# Expansor_conn.net
KiCad netlist of a schematic drawn in Altium Designer
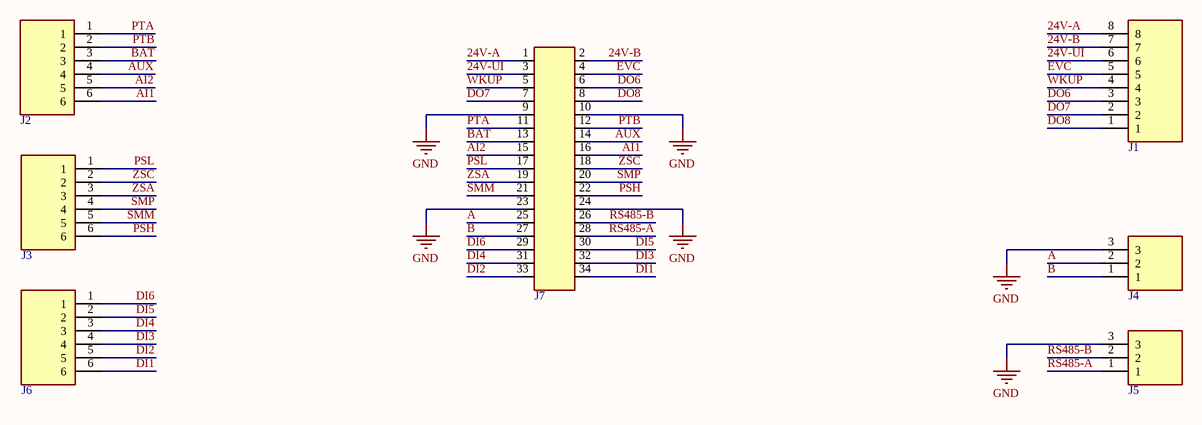
[diagram p0: Expansor_conn.SchDoc]

(export (version "E")
  (design (tool "Eeschema 10.0.6"))
  (components
    (comp (ref "J1")
      (value "HDRF8")
      (footprint "HDR_F_1X8")
      (description "CONN, HEADER, Female, pitch: 2.54mm, 8POS")
      (libsource (lib "Headers") (part "Header Female 1x8 THT"))
    )
    (comp (ref "J2")
      (value "HDRF6")
      (footprint "HDR_F_1X6")
      (description "CONN, HEADER, Female, pitch: 2.54mm, 6POS")
      (libsource (lib "Headers") (part "Header Female 1x6 THT"))
    )
    (comp (ref "J3")
      (value "HDRF6")
      (footprint "HDR_F_1X6")
      (description "CONN, HEADER, Female, pitch: 2.54mm, 6POS")
      (libsource (lib "Headers") (part "Header Female 1x6 THT"))
    )
    (comp (ref "J4")
      (value "HDRF3")
      (footprint "HDR_F_1X3")
      (description "CONN, HEADER, Female, pitch: 2.54mm, 3POS")
      (libsource (lib "Headers") (part "Header Female 1x3 THT"))
    )
    (comp (ref "J5")
      (value "HDRF3")
      (footprint "HDR_F_1X3")
      (description "CONN, HEADER, Female, pitch: 2.54mm, 3POS")
      (libsource (lib "Headers") (part "Header Female 1x3 THT"))
    )
    (comp (ref "J6")
      (value "HDRF6")
      (footprint "HDR_F_1X6")
      (description "CONN, HEADER, Female, pitch: 2.54mm, 6POS")
      (libsource (lib "Headers") (part "Header Female 1x6 THT"))
    )
    (comp (ref "J7")
      (value "6120XX21621_61203421621")
      (footprint "61203421621")
      (description "34 pins, straight, gold plating")
      (fields (field (name "MF") "Wurth Electronics") (field (name "MP") "61203421621"))
      (libsource (lib "Base_borne_MEP_1") (part "6120XX21621_61203421621"))
    )
  )
  (nets
    (net (code "1") (name "/24V-A") (class "Default")
      (node (ref "J1") (pin "8") (pinfunction "8_8") (pintype "passive"))
      (node (ref "J7") (pin "1") (pinfunction "1_1") (pintype "passive"))
    )
    (net (code "2") (name "/24V-B") (class "Default")
      (node (ref "J1") (pin "7") (pinfunction "7_7") (pintype "passive"))
      (node (ref "J7") (pin "2") (pinfunction "2_2") (pintype "passive"))
    )
    (net (code "3") (name "/24V-UI") (class "Default")
      (node (ref "J1") (pin "6") (pinfunction "6_6") (pintype "passive"))
      (node (ref "J7") (pin "3") (pinfunction "3_3") (pintype "passive"))
    )
    (net (code "4") (name "/A") (class "Default")
      (node (ref "J4") (pin "2") (pinfunction "2_2") (pintype "passive"))
      (node (ref "J7") (pin "25") (pinfunction "25_25") (pintype "passive"))
    )
    (net (code "5") (name "/AI1") (class "Default")
      (node (ref "J2") (pin "6") (pinfunction "6_6") (pintype "passive"))
      (node (ref "J7") (pin "16") (pinfunction "16_16") (pintype "passive"))
    )
    (net (code "6") (name "/AI2") (class "Default")
      (node (ref "J2") (pin "5") (pinfunction "5_5") (pintype "passive"))
      (node (ref "J7") (pin "15") (pinfunction "15_15") (pintype "passive"))
    )
    (net (code "7") (name "/AUX") (class "Default")
      (node (ref "J2") (pin "4") (pinfunction "4_4") (pintype "passive"))
      (node (ref "J7") (pin "14") (pinfunction "14_14") (pintype "passive"))
    )
    (net (code "8") (name "/B") (class "Default")
      (node (ref "J4") (pin "1") (pinfunction "1_1") (pintype "passive"))
      (node (ref "J7") (pin "27") (pinfunction "27_27") (pintype "passive"))
    )
    (net (code "9") (name "/BAT") (class "Default")
      (node (ref "J2") (pin "3") (pinfunction "3_3") (pintype "passive"))
      (node (ref "J7") (pin "13") (pinfunction "13_13") (pintype "passive"))
    )
    (net (code "10") (name "/DI1") (class "Default")
      (node (ref "J6") (pin "6") (pinfunction "6_6") (pintype "passive"))
      (node (ref "J7") (pin "34") (pinfunction "34_34") (pintype "passive"))
    )
    (net (code "11") (name "/DI2") (class "Default")
      (node (ref "J6") (pin "5") (pinfunction "5_5") (pintype "passive"))
      (node (ref "J7") (pin "33") (pinfunction "33_33") (pintype "passive"))
    )
    (net (code "12") (name "/DI3") (class "Default")
      (node (ref "J6") (pin "4") (pinfunction "4_4") (pintype "passive"))
      (node (ref "J7") (pin "32") (pinfunction "32_32") (pintype "passive"))
    )
    (net (code "13") (name "/DI4") (class "Default")
      (node (ref "J6") (pin "3") (pinfunction "3_3") (pintype "passive"))
      (node (ref "J7") (pin "31") (pinfunction "31_31") (pintype "passive"))
    )
    (net (code "14") (name "/DI5") (class "Default")
      (node (ref "J6") (pin "2") (pinfunction "2_2") (pintype "passive"))
      (node (ref "J7") (pin "30") (pinfunction "30_30") (pintype "passive"))
    )
    (net (code "15") (name "/DI6") (class "Default")
      (node (ref "J6") (pin "1") (pinfunction "1_1") (pintype "passive"))
      (node (ref "J7") (pin "29") (pinfunction "29_29") (pintype "passive"))
    )
    (net (code "16") (name "/DO6") (class "Default")
      (node (ref "J1") (pin "3") (pinfunction "3_3") (pintype "passive"))
      (node (ref "J7") (pin "6") (pinfunction "6_6") (pintype "passive"))
    )
    (net (code "17") (name "/DO7") (class "Default")
      (node (ref "J1") (pin "2") (pinfunction "2_2") (pintype "passive"))
      (node (ref "J7") (pin "7") (pinfunction "7_7") (pintype "passive"))
    )
    (net (code "18") (name "/DO8") (class "Default")
      (node (ref "J1") (pin "1") (pinfunction "1_1") (pintype "passive"))
      (node (ref "J7") (pin "8") (pinfunction "8_8") (pintype "passive"))
    )
    (net (code "19") (name "/EVC") (class "Default")
      (node (ref "J1") (pin "5") (pinfunction "5_5") (pintype "passive"))
      (node (ref "J7") (pin "4") (pinfunction "4_4") (pintype "passive"))
    )
    (net (code "20") (name "/PSH") (class "Default")
      (node (ref "J3") (pin "6") (pinfunction "6_6") (pintype "passive"))
      (node (ref "J7") (pin "22") (pinfunction "22_22") (pintype "passive"))
    )
    (net (code "21") (name "/PSL") (class "Default")
      (node (ref "J3") (pin "1") (pinfunction "1_1") (pintype "passive"))
      (node (ref "J7") (pin "17") (pinfunction "17_17") (pintype "passive"))
    )
    (net (code "22") (name "/PTA") (class "Default")
      (node (ref "J2") (pin "1") (pinfunction "1_1") (pintype "passive"))
      (node (ref "J7") (pin "11") (pinfunction "11_11") (pintype "passive"))
    )
    (net (code "23") (name "/PTB") (class "Default")
      (node (ref "J2") (pin "2") (pinfunction "2_2") (pintype "passive"))
      (node (ref "J7") (pin "12") (pinfunction "12_12") (pintype "passive"))
    )
    (net (code "24") (name "/RS485-A") (class "Default")
      (node (ref "J5") (pin "1") (pinfunction "1_1") (pintype "passive"))
      (node (ref "J7") (pin "28") (pinfunction "28_28") (pintype "passive"))
    )
    (net (code "25") (name "/RS485-B") (class "Default")
      (node (ref "J5") (pin "2") (pinfunction "2_2") (pintype "passive"))
      (node (ref "J7") (pin "26") (pinfunction "26_26") (pintype "passive"))
    )
    (net (code "26") (name "/SMM") (class "Default")
      (node (ref "J3") (pin "5") (pinfunction "5_5") (pintype "passive"))
      (node (ref "J7") (pin "21") (pinfunction "21_21") (pintype "passive"))
    )
    (net (code "27") (name "/SMP") (class "Default")
      (node (ref "J3") (pin "4") (pinfunction "4_4") (pintype "passive"))
      (node (ref "J7") (pin "20") (pinfunction "20_20") (pintype "passive"))
    )
    (net (code "28") (name "/WKUP") (class "Default")
      (node (ref "J1") (pin "4") (pinfunction "4_4") (pintype "passive"))
      (node (ref "J7") (pin "5") (pinfunction "5_5") (pintype "passive"))
    )
    (net (code "29") (name "/ZSA") (class "Default")
      (node (ref "J3") (pin "3") (pinfunction "3_3") (pintype "passive"))
      (node (ref "J7") (pin "19") (pinfunction "19_19") (pintype "passive"))
    )
    (net (code "30") (name "/ZSC") (class "Default")
      (node (ref "J3") (pin "2") (pinfunction "2_2") (pintype "passive"))
      (node (ref "J7") (pin "18") (pinfunction "18_18") (pintype "passive"))
    )
    (net (code "31") (name "GND") (class "Default")
      (node (ref "J4") (pin "3") (pinfunction "3_3") (pintype "passive"))
      (node (ref "J5") (pin "3") (pinfunction "3_3") (pintype "passive"))
      (node (ref "J7") (pin "10") (pinfunction "10_10") (pintype "passive"))
      (node (ref "J7") (pin "23") (pinfunction "23_23") (pintype "passive"))
      (node (ref "J7") (pin "24") (pinfunction "24_24") (pintype "passive"))
      (node (ref "J7") (pin "9") (pinfunction "9_9") (pintype "passive"))
    )
  )
)
